# etapa5.net
KiCad netlist of a schematic drawn in Altium Designer
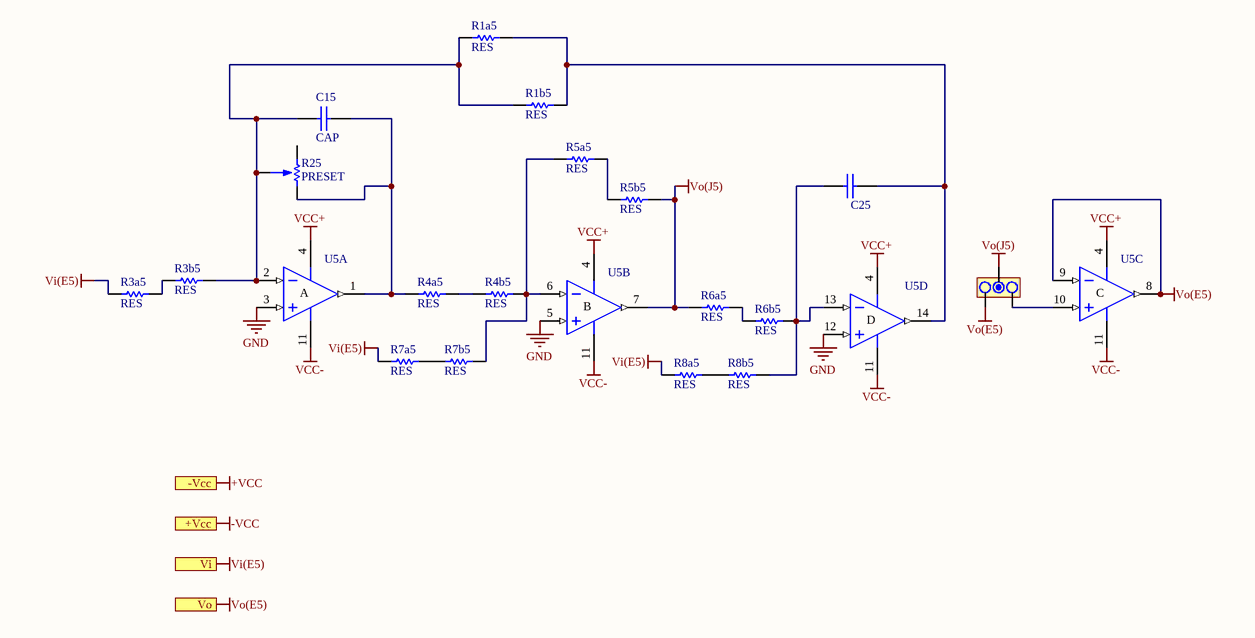
[diagram p0: etapa5.SchDoc]

(export (version "E")
  (design (tool "Eeschema 10.0.6"))
  (components
    (comp (ref "C15") (value "CAP") (footprint "CAP200") (libsource (lib "LIBEBAL") (part "CAP")))
    (comp (ref "C25") (value "CAP") (footprint "CAP200") (libsource (lib "LIBEBAL") (part "CAP")))
    (comp (ref "Jumper5") (value "JUMPER") (footprint "JUMPER3") (libsource (lib "LIBEBAL") (part "JUMPER3")))
    (comp (ref "R1a5") (value "RES") (footprint "0805") (libsource (lib "LIBEBAL") (part "RES")))
    (comp (ref "R1b5") (value "RES") (footprint "0805") (libsource (lib "LIBEBAL") (part "RES")))
    (comp (ref "R3a5") (value "RES") (footprint "0805") (libsource (lib "LIBEBAL") (part "RES")))
    (comp (ref "R3b5") (value "RES") (footprint "0805") (libsource (lib "LIBEBAL") (part "RES")))
    (comp (ref "R4a5") (value "RES") (footprint "0805") (libsource (lib "LIBEBAL") (part "RES")))
    (comp (ref "R4b5") (value "RES") (footprint "0805") (libsource (lib "LIBEBAL") (part "RES")))
    (comp (ref "R5a5") (value "RES") (footprint "0805") (libsource (lib "LIBEBAL") (part "RES")))
    (comp (ref "R5b5") (value "RES") (footprint "0805") (libsource (lib "LIBEBAL") (part "RES")))
    (comp (ref "R6a5") (value "RES") (footprint "0805") (libsource (lib "LIBEBAL") (part "RES")))
    (comp (ref "R6b5") (value "RES") (footprint "0805") (libsource (lib "LIBEBAL") (part "RES")))
    (comp (ref "R7a5") (value "RES") (footprint "0805") (libsource (lib "LIBEBAL") (part "RES")))
    (comp (ref "R7b5") (value "RES") (footprint "0805") (libsource (lib "LIBEBAL") (part "RES")))
    (comp (ref "R8a5") (value "RES") (footprint "0805") (libsource (lib "LIBEBAL") (part "RES")))
    (comp (ref "R8b5") (value "RES") (footprint "0805") (libsource (lib "LIBEBAL") (part "RES")))
    (comp (ref "R25") (value "PRESET") (footprint "PRESET V") (libsource (lib "LIBEBAL") (part "PRESET")))
    (comp (ref "U5")
      (value "TL084N")
      (footprint "N014")
      (description "JFET-Input Operational Amplifier")
      (fields (field (name "PUBLISHER") "Altium Limited"))
      (libsource (lib "TI Operational Amplifier") (part "TL084N"))
    )
  )
  (nets
    (net (code "3") (name "GND") (class "Default")
      (node (ref "U5") (pin "12") (pinfunction "IN+_12") (pintype "input"))
      (node (ref "U5") (pin "3") (pinfunction "IN+_3") (pintype "input"))
      (node (ref "U5") (pin "5") (pinfunction "IN+_5") (pintype "input"))
    )
    (net (code "4") (name "Net-(R3a5-Pad2)") (class "Default")
      (node (ref "R3a5") (pin "2") (pinfunction "2_2") (pintype "passive"))
      (node (ref "R3b5") (pin "1") (pinfunction "1_1") (pintype "passive"))
    )
    (net (code "5") (name "Net-(R4a5-Pad2)") (class "Default")
      (node (ref "R4a5") (pin "2") (pinfunction "2_2") (pintype "passive"))
      (node (ref "R4b5") (pin "1") (pinfunction "1_1") (pintype "passive"))
    )
    (net (code "6") (name "Net-(R5a5-Pad2)") (class "Default")
      (node (ref "R5a5") (pin "2") (pinfunction "2_2") (pintype "passive"))
      (node (ref "R5b5") (pin "1") (pinfunction "1_1") (pintype "passive"))
    )
    (net (code "7") (name "Net-(R6a5-Pad2)") (class "Default")
      (node (ref "R6a5") (pin "2") (pinfunction "2_2") (pintype "passive"))
      (node (ref "R6b5") (pin "1") (pinfunction "1_1") (pintype "passive"))
    )
    (net (code "8") (name "Net-(R7a5-Pad2)") (class "Default")
      (node (ref "R7a5") (pin "2") (pinfunction "2_2") (pintype "passive"))
      (node (ref "R7b5") (pin "1") (pinfunction "1_1") (pintype "passive"))
    )
    (net (code "9") (name "Net-(R8a5-Pad2)") (class "Default")
      (node (ref "R8a5") (pin "2") (pinfunction "2_2") (pintype "passive"))
      (node (ref "R8b5") (pin "1") (pinfunction "1_1") (pintype "passive"))
    )
    (net (code "10") (name "Net-(U5A-IN-)") (class "Default")
      (node (ref "C15") (pin "1") (pinfunction "1_1") (pintype "passive"))
      (node (ref "R1a5") (pin "1") (pinfunction "1_1") (pintype "passive"))
      (node (ref "R1b5") (pin "1") (pinfunction "1_1") (pintype "passive"))
      (node (ref "R25") (pin "2") (pinfunction "2_2") (pintype "passive"))
      (node (ref "R3b5") (pin "2") (pinfunction "2_2") (pintype "passive"))
      (node (ref "U5") (pin "2") (pinfunction "IN-_2") (pintype "input"))
    )
    (net (code "11") (name "Net-(U5A-OUT)") (class "Default")
      (node (ref "C15") (pin "2") (pinfunction "2_2") (pintype "passive"))
      (node (ref "R25") (pin "1") (pinfunction "1_1") (pintype "passive"))
      (node (ref "R4a5") (pin "1") (pinfunction "1_1") (pintype "passive"))
      (node (ref "U5") (pin "1") (pinfunction "OUT_1") (pintype "output"))
    )
    (net (code "12") (name "Net-(U5B-IN-)") (class "Default")
      (node (ref "R4b5") (pin "2") (pinfunction "2_2") (pintype "passive"))
      (node (ref "R5a5") (pin "1") (pinfunction "1_1") (pintype "passive"))
      (node (ref "R7b5") (pin "2") (pinfunction "2_2") (pintype "passive"))
      (node (ref "U5") (pin "6") (pinfunction "IN-_6") (pintype "input"))
    )
    (net (code "13") (name "Net-(U5C-IN+)") (class "Default")
      (node (ref "Jumper5") (pin "1") (pinfunction "1_1") (pintype "passive"))
      (node (ref "U5") (pin "10") (pinfunction "IN+_10") (pintype "input"))
    )
    (net (code "14") (name "Net-(U5D-IN-)") (class "Default")
      (node (ref "C25") (pin "1") (pinfunction "1_1") (pintype "passive"))
      (node (ref "R6b5") (pin "2") (pinfunction "2_2") (pintype "passive"))
      (node (ref "R8b5") (pin "2") (pinfunction "2_2") (pintype "passive"))
      (node (ref "U5") (pin "13") (pinfunction "IN-_13") (pintype "input"))
    )
    (net (code "15") (name "Net-(U5D-OUT)") (class "Default")
      (node (ref "C25") (pin "2") (pinfunction "2_2") (pintype "passive"))
      (node (ref "R1a5") (pin "2") (pinfunction "2_2") (pintype "passive"))
      (node (ref "R1b5") (pin "2") (pinfunction "2_2") (pintype "passive"))
      (node (ref "U5") (pin "14") (pinfunction "OUT_14") (pintype "output"))
    )
    (net (code "16") (name "VCC+") (class "Default")
      (node (ref "U5") (pin "4") (pinfunction "V+_4") (pintype "power_in"))
    )
    (net (code "17") (name "VCC-") (class "Default")
      (node (ref "U5") (pin "11") (pinfunction "V-_11") (pintype "power_in"))
    )
    (net (code "18") (name "Vi(E5)") (class "Default")
      (node (ref "R3a5") (pin "1") (pinfunction "1_1") (pintype "passive"))
      (node (ref "R7a5") (pin "1") (pinfunction "1_1") (pintype "passive"))
      (node (ref "R8a5") (pin "1") (pinfunction "1_1") (pintype "passive"))
    )
    (net (code "19") (name "Vo(E5)") (class "Default")
      (node (ref "Jumper5") (pin "3") (pinfunction "3_3") (pintype "passive"))
      (node (ref "U5") (pin "8") (pinfunction "OUT_8") (pintype "output"))
      (node (ref "U5") (pin "9") (pinfunction "IN-_9") (pintype "input"))
    )
    (net (code "20") (name "Vo(J5)") (class "Default")
      (node (ref "Jumper5") (pin "2") (pinfunction "2_2") (pintype "passive"))
      (node (ref "R5b5") (pin "2") (pinfunction "2_2") (pintype "passive"))
      (node (ref "R6a5") (pin "1") (pinfunction "1_1") (pintype "passive"))
      (node (ref "U5") (pin "7") (pinfunction "OUT_7") (pintype "output"))
    )
    (net (code "21") (name "unconnected-(R25-Pad3)") (class "Default")
      (node (ref "R25") (pin "3") (pinfunction "3_3") (pintype "passive"))
    )
  )
)
